# ORS-Bluefruit-BLE-Dongle-v0_01.net
KiCad netlist of a schematic drawn in EAGLE
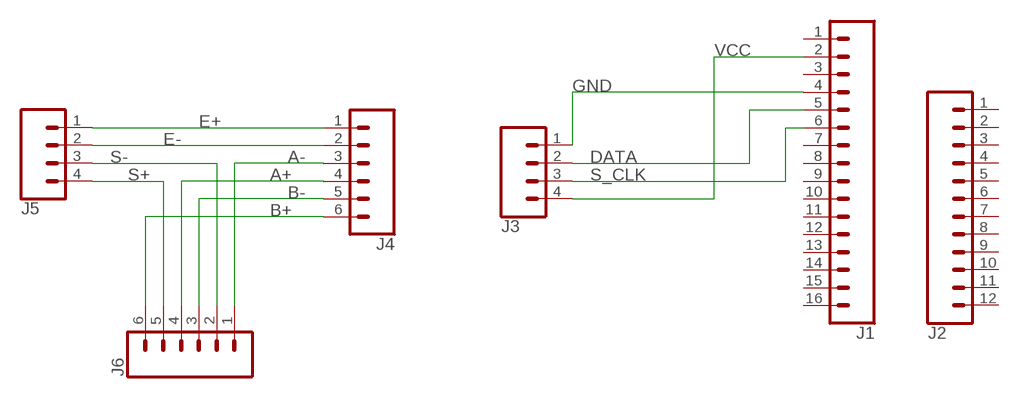
[diagram p0: schematic, sheet 1]

(export (version "E")
  (design (tool "Eeschema 10.0.6"))
  (components
    (comp (ref "J1")
      (value "CONN_16")
      (footprint "eagle-import:1X16")
      (libsource (lib "eagle-import") (part "CONN_16"))
    )
    (comp (ref "J2")
      (value "CONN_12")
      (footprint "eagle-import:1X12")
      (libsource (lib "eagle-import") (part "CONN_12"))
    )
    (comp (ref "J3")
      (value "CONN_04")
      (footprint "eagle-import:1X04")
      (libsource (lib "eagle-import") (part "CONN_04"))
    )
    (comp (ref "J4")
      (value "CONN_06SILK_FEMALE_PTH")
      (footprint "eagle-import:1X06")
      (libsource (lib "eagle-import") (part "CONN_06SILK_FEMALE_PTH"))
    )
    (comp (ref "J5")
      (value "CONN_04SCREW")
      (footprint "eagle-import:SCREWTERMINAL-3.5MM-4")
      (libsource (lib "eagle-import") (part "CONN_04SCREW"))
    )
    (comp (ref "J6")
      (value "CONN_06SILK_FEMALE_PTH")
      (footprint "eagle-import:1X06")
      (libsource (lib "eagle-import") (part "CONN_06SILK_FEMALE_PTH"))
    )
  )
  (nets
    (net (code "1") (name "/A+") (class "Default")
      (node (ref "J4") (pin "4") (pinfunction "4_4") (pintype "passive"))
      (node (ref "J6") (pin "4") (pinfunction "4_4") (pintype "passive"))
    )
    (net (code "2") (name "/A-") (class "Default")
      (node (ref "J4") (pin "3") (pinfunction "3_3") (pintype "passive"))
      (node (ref "J6") (pin "1") (pinfunction "1_1") (pintype "passive"))
    )
    (net (code "3") (name "/B+") (class "Default")
      (node (ref "J4") (pin "6") (pinfunction "6_6") (pintype "passive"))
      (node (ref "J6") (pin "6") (pinfunction "6_6") (pintype "passive"))
    )
    (net (code "4") (name "/B-") (class "Default")
      (node (ref "J4") (pin "5") (pinfunction "5_5") (pintype "passive"))
      (node (ref "J6") (pin "3") (pinfunction "3_3") (pintype "passive"))
    )
    (net (code "5") (name "/DATA") (class "Default")
      (node (ref "J1") (pin "5") (pinfunction "5_5") (pintype "passive"))
      (node (ref "J3") (pin "2") (pinfunction "2_2") (pintype "passive"))
    )
    (net (code "6") (name "/E+") (class "Default")
      (node (ref "J4") (pin "1") (pinfunction "1_1") (pintype "passive"))
      (node (ref "J5") (pin "1") (pinfunction "1_1") (pintype "passive"))
    )
    (net (code "7") (name "/E-") (class "Default")
      (node (ref "J4") (pin "2") (pinfunction "2_2") (pintype "passive"))
      (node (ref "J5") (pin "2") (pinfunction "2_2") (pintype "passive"))
    )
    (net (code "8") (name "/GND") (class "Default")
      (node (ref "J1") (pin "4") (pinfunction "4_4") (pintype "passive"))
      (node (ref "J3") (pin "1") (pinfunction "1_1") (pintype "passive"))
    )
    (net (code "9") (name "/S+") (class "Default")
      (node (ref "J5") (pin "4") (pinfunction "4_4") (pintype "passive"))
      (node (ref "J6") (pin "5") (pinfunction "5_5") (pintype "passive"))
    )
    (net (code "10") (name "/S-") (class "Default")
      (node (ref "J5") (pin "3") (pinfunction "3_3") (pintype "passive"))
      (node (ref "J6") (pin "2") (pinfunction "2_2") (pintype "passive"))
    )
    (net (code "11") (name "/S_CLK") (class "Default")
      (node (ref "J1") (pin "6") (pinfunction "6_6") (pintype "passive"))
      (node (ref "J3") (pin "3") (pinfunction "3_3") (pintype "passive"))
    )
    (net (code "12") (name "/VCC") (class "Default")
      (node (ref "J1") (pin "2") (pinfunction "2_2") (pintype "passive"))
      (node (ref "J3") (pin "4") (pinfunction "4_4") (pintype "passive"))
    )
    (net (code "13") (name "unconnected-(J1-Pad1)") (class "Default")
      (node (ref "J1") (pin "1") (pinfunction "1_1") (pintype "passive"))
    )
    (net (code "14") (name "unconnected-(J1-Pad3)") (class "Default")
      (node (ref "J1") (pin "3") (pinfunction "3_3") (pintype "passive"))
    )
    (net (code "15") (name "unconnected-(J1-Pad7)") (class "Default")
      (node (ref "J1") (pin "7") (pinfunction "7_7") (pintype "passive"))
    )
    (net (code "16") (name "unconnected-(J1-Pad8)") (class "Default")
      (node (ref "J1") (pin "8") (pinfunction "8_8") (pintype "passive"))
    )
    (net (code "17") (name "unconnected-(J1-Pad9)") (class "Default")
      (node (ref "J1") (pin "9") (pinfunction "9_9") (pintype "passive"))
    )
    (net (code "18") (name "unconnected-(J1-Pad10)") (class "Default")
      (node (ref "J1") (pin "10") (pinfunction "10_10") (pintype "passive"))
    )
    (net (code "19") (name "unconnected-(J1-Pad11)") (class "Default")
      (node (ref "J1") (pin "11") (pinfunction "11_11") (pintype "passive"))
    )
    (net (code "20") (name "unconnected-(J1-Pad12)") (class "Default")
      (node (ref "J1") (pin "12") (pinfunction "12_12") (pintype "passive"))
    )
    (net (code "21") (name "unconnected-(J1-Pad13)") (class "Default")
      (node (ref "J1") (pin "13") (pinfunction "13_13") (pintype "passive"))
    )
    (net (code "22") (name "unconnected-(J1-Pad14)") (class "Default")
      (node (ref "J1") (pin "14") (pinfunction "14_14") (pintype "passive"))
    )
    (net (code "23") (name "unconnected-(J1-Pad15)") (class "Default")
      (node (ref "J1") (pin "15") (pinfunction "15_15") (pintype "passive"))
    )
    (net (code "24") (name "unconnected-(J1-Pad16)") (class "Default")
      (node (ref "J1") (pin "16") (pinfunction "16_16") (pintype "passive"))
    )
    (net (code "25") (name "unconnected-(J2-Pad1)") (class "Default")
      (node (ref "J2") (pin "1") (pinfunction "1_1") (pintype "passive"))
    )
    (net (code "26") (name "unconnected-(J2-Pad2)") (class "Default")
      (node (ref "J2") (pin "2") (pinfunction "2_2") (pintype "passive"))
    )
    (net (code "27") (name "unconnected-(J2-Pad3)") (class "Default")
      (node (ref "J2") (pin "3") (pinfunction "3_3") (pintype "passive"))
    )
    (net (code "28") (name "unconnected-(J2-Pad4)") (class "Default")
      (node (ref "J2") (pin "4") (pinfunction "4_4") (pintype "passive"))
    )
    (net (code "29") (name "unconnected-(J2-Pad5)") (class "Default")
      (node (ref "J2") (pin "5") (pinfunction "5_5") (pintype "passive"))
    )
    (net (code "30") (name "unconnected-(J2-Pad6)") (class "Default")
      (node (ref "J2") (pin "6") (pinfunction "6_6") (pintype "passive"))
    )
    (net (code "31") (name "unconnected-(J2-Pad7)") (class "Default")
      (node (ref "J2") (pin "7") (pinfunction "7_7") (pintype "passive"))
    )
    (net (code "32") (name "unconnected-(J2-Pad8)") (class "Default")
      (node (ref "J2") (pin "8") (pinfunction "8_8") (pintype "passive"))
    )
    (net (code "33") (name "unconnected-(J2-Pad9)") (class "Default")
      (node (ref "J2") (pin "9") (pinfunction "9_9") (pintype "passive"))
    )
    (net (code "34") (name "unconnected-(J2-Pad10)") (class "Default")
      (node (ref "J2") (pin "10") (pinfunction "10_10") (pintype "passive"))
    )
    (net (code "35") (name "unconnected-(J2-Pad11)") (class "Default")
      (node (ref "J2") (pin "11") (pinfunction "11_11") (pintype "passive"))
    )
    (net (code "36") (name "unconnected-(J2-Pad12)") (class "Default")
      (node (ref "J2") (pin "12") (pinfunction "12_12") (pintype "passive"))
    )
  )
)
